# A607X.net
KiCad netlist of a schematic drawn in EAGLE
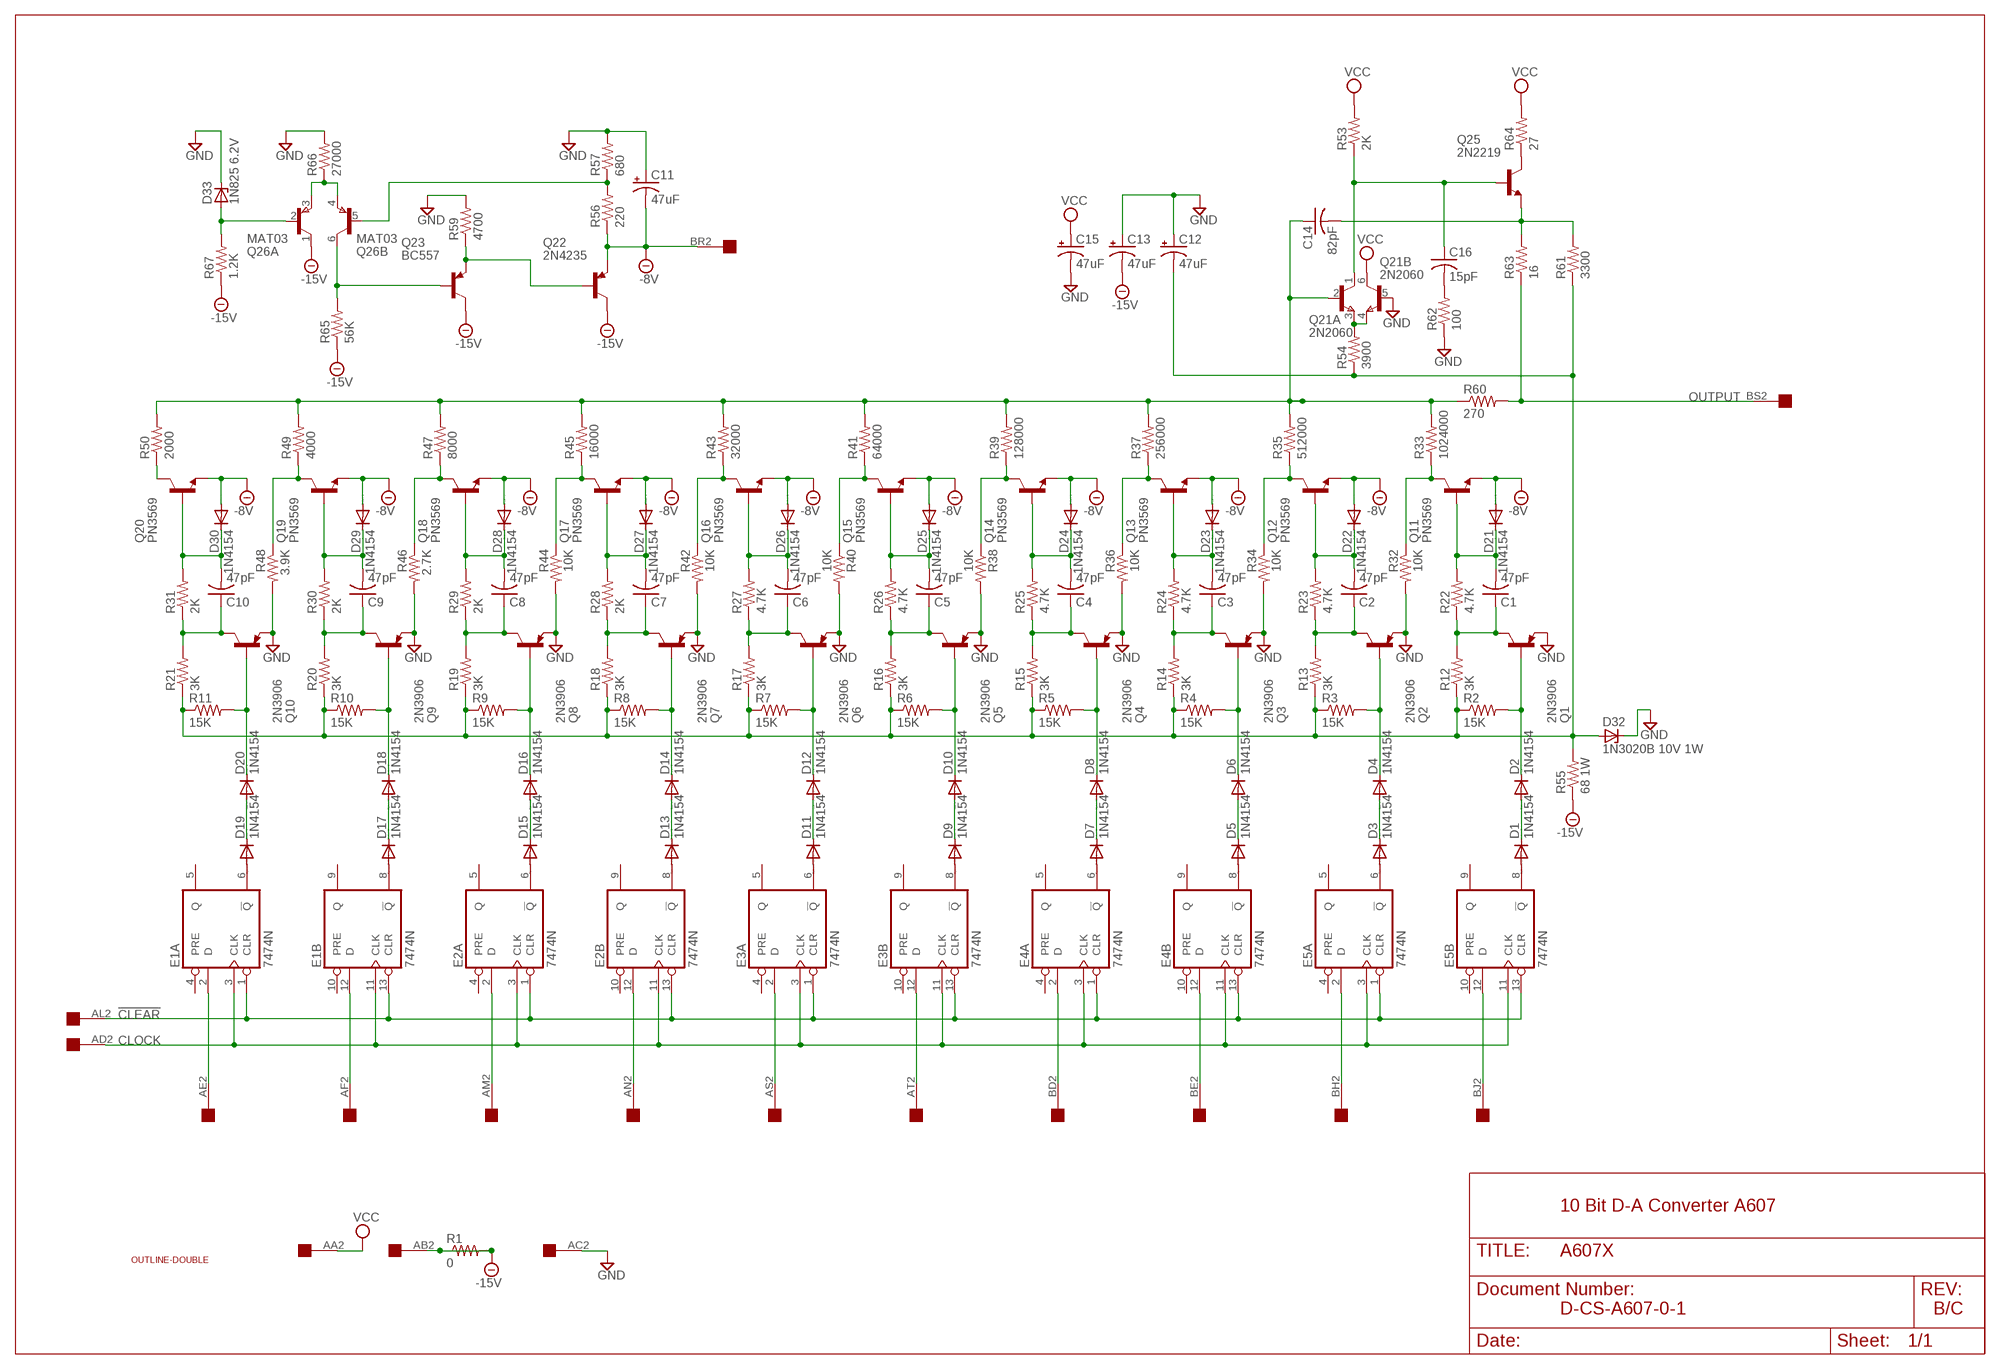
[diagram p0: schematic, sheet 1]

(export (version "E")
  (design (tool "Eeschema 10.0.6"))
  (components
    (comp (ref "C1")
      (value "47pF")
      (footprint "eagle-import:C075-032X103")
      (libsource (lib "eagle-import") (part "C-US075-032X103"))
    )
    (comp (ref "C2")
      (value "47pF")
      (footprint "eagle-import:C075-032X103")
      (libsource (lib "eagle-import") (part "C-US075-032X103"))
    )
    (comp (ref "C3")
      (value "47pF")
      (footprint "eagle-import:C075-032X103")
      (libsource (lib "eagle-import") (part "C-US075-032X103"))
    )
    (comp (ref "C4")
      (value "47pF")
      (footprint "eagle-import:C075-032X103")
      (libsource (lib "eagle-import") (part "C-US075-032X103"))
    )
    (comp (ref "C5")
      (value "47pF")
      (footprint "eagle-import:C075-032X103")
      (libsource (lib "eagle-import") (part "C-US075-032X103"))
    )
    (comp (ref "C6")
      (value "47pF")
      (footprint "eagle-import:C075-032X103")
      (libsource (lib "eagle-import") (part "C-US075-032X103"))
    )
    (comp (ref "C7")
      (value "47pF")
      (footprint "eagle-import:C075-032X103")
      (libsource (lib "eagle-import") (part "C-US075-032X103"))
    )
    (comp (ref "C8")
      (value "47pF")
      (footprint "eagle-import:C075-032X103")
      (libsource (lib "eagle-import") (part "C-US075-032X103"))
    )
    (comp (ref "C9")
      (value "47pF")
      (footprint "eagle-import:C075-032X103")
      (libsource (lib "eagle-import") (part "C-US075-032X103"))
    )
    (comp (ref "C10")
      (value "47pF")
      (footprint "eagle-import:C075-032X103")
      (libsource (lib "eagle-import") (part "C-US075-032X103"))
    )
    (comp (ref "C11")
      (value "47uF")
      (footprint "eagle-import:E25-9")
      (libsource (lib "eagle-import") (part "CPOL-USE25-9AXIAL"))
    )
    (comp (ref "C12")
      (value "47uF")
      (footprint "eagle-import:E25-9")
      (libsource (lib "eagle-import") (part "CPOL-USE25-9AXIAL"))
    )
    (comp (ref "C13")
      (value "47uF")
      (footprint "eagle-import:E25-9")
      (libsource (lib "eagle-import") (part "CPOL-USE25-9AXIAL"))
    )
    (comp (ref "C14")
      (value "82pF")
      (footprint "eagle-import:C050-025X075")
      (libsource (lib "eagle-import") (part "C-US050-025X075"))
    )
    (comp (ref "C15")
      (value "47uF")
      (footprint "eagle-import:E25-9")
      (libsource (lib "eagle-import") (part "CPOL-USE25-9AXIAL"))
    )
    (comp (ref "C16")
      (value "15pF")
      (footprint "eagle-import:C050-025X075")
      (libsource (lib "eagle-import") (part "C-US050-025X075"))
    )
    (comp (ref "D1")
      (value "1N4154")
      (footprint "eagle-import:DO35-10")
      (libsource (lib "eagle-import") (part "DIODE-DO35-10"))
    )
    (comp (ref "D2")
      (value "1N4154")
      (footprint "eagle-import:DO35-10")
      (libsource (lib "eagle-import") (part "DIODE-DO35-10"))
    )
    (comp (ref "D3")
      (value "1N4154")
      (footprint "eagle-import:DO35-10")
      (libsource (lib "eagle-import") (part "DIODE-DO35-10"))
    )
    (comp (ref "D4")
      (value "1N4154")
      (footprint "eagle-import:DO35-10")
      (libsource (lib "eagle-import") (part "DIODE-DO35-10"))
    )
    (comp (ref "D5")
      (value "1N4154")
      (footprint "eagle-import:DO35-10")
      (libsource (lib "eagle-import") (part "DIODE-DO35-10"))
    )
    (comp (ref "D6")
      (value "1N4154")
      (footprint "eagle-import:DO35-10")
      (libsource (lib "eagle-import") (part "DIODE-DO35-10"))
    )
    (comp (ref "D7")
      (value "1N4154")
      (footprint "eagle-import:DO35-10")
      (libsource (lib "eagle-import") (part "DIODE-DO35-10"))
    )
    (comp (ref "D8")
      (value "1N4154")
      (footprint "eagle-import:DO35-10")
      (libsource (lib "eagle-import") (part "DIODE-DO35-10"))
    )
    (comp (ref "D9")
      (value "1N4154")
      (footprint "eagle-import:DO35-10")
      (libsource (lib "eagle-import") (part "DIODE-DO35-10"))
    )
    (comp (ref "D10")
      (value "1N4154")
      (footprint "eagle-import:DO35-10")
      (libsource (lib "eagle-import") (part "DIODE-DO35-10"))
    )
    (comp (ref "D11")
      (value "1N4154")
      (footprint "eagle-import:DO35-10")
      (libsource (lib "eagle-import") (part "DIODE-DO35-10"))
    )
    (comp (ref "D12")
      (value "1N4154")
      (footprint "eagle-import:DO35-10")
      (libsource (lib "eagle-import") (part "DIODE-DO35-10"))
    )
    (comp (ref "D13")
      (value "1N4154")
      (footprint "eagle-import:DO35-10")
      (libsource (lib "eagle-import") (part "DIODE-DO35-10"))
    )
    (comp (ref "D14")
      (value "1N4154")
      (footprint "eagle-import:DO35-10")
      (libsource (lib "eagle-import") (part "DIODE-DO35-10"))
    )
    (comp (ref "D15")
      (value "1N4154")
      (footprint "eagle-import:DO35-10")
      (libsource (lib "eagle-import") (part "DIODE-DO35-10"))
    )
    (comp (ref "D16")
      (value "1N4154")
      (footprint "eagle-import:DO35-10")
      (libsource (lib "eagle-import") (part "DIODE-DO35-10"))
    )
    (comp (ref "D17")
      (value "1N4154")
      (footprint "eagle-import:DO35-10")
      (libsource (lib "eagle-import") (part "DIODE-DO35-10"))
    )
    (comp (ref "D18")
      (value "1N4154")
      (footprint "eagle-import:DO35-10")
      (libsource (lib "eagle-import") (part "DIODE-DO35-10"))
    )
    (comp (ref "D19")
      (value "1N4154")
      (footprint "eagle-import:DO35-10")
      (libsource (lib "eagle-import") (part "DIODE-DO35-10"))
    )
    (comp (ref "D20")
      (value "1N4154")
      (footprint "eagle-import:DO35-10")
      (libsource (lib "eagle-import") (part "DIODE-DO35-10"))
    )
    (comp (ref "D21")
      (value "1N4154")
      (footprint "eagle-import:DO35-10")
      (libsource (lib "eagle-import") (part "DIODE-DO35-10"))
    )
    (comp (ref "D22")
      (value "1N4154")
      (footprint "eagle-import:DO35-10")
      (libsource (lib "eagle-import") (part "DIODE-DO35-10"))
    )
    (comp (ref "D23")
      (value "1N4154")
      (footprint "eagle-import:DO35-10")
      (libsource (lib "eagle-import") (part "DIODE-DO35-10"))
    )
    (comp (ref "D24")
      (value "1N4154")
      (footprint "eagle-import:DO35-10")
      (libsource (lib "eagle-import") (part "DIODE-DO35-10"))
    )
    (comp (ref "D25")
      (value "1N4154")
      (footprint "eagle-import:DO35-10")
      (libsource (lib "eagle-import") (part "DIODE-DO35-10"))
    )
    (comp (ref "D26")
      (value "1N4154")
      (footprint "eagle-import:DO35-10")
      (libsource (lib "eagle-import") (part "DIODE-DO35-10"))
    )
    (comp (ref "D27")
      (value "1N4154")
      (footprint "eagle-import:DO35-10")
      (libsource (lib "eagle-import") (part "DIODE-DO35-10"))
    )
    (comp (ref "D28")
      (value "1N4154")
      (footprint "eagle-import:DO35-10")
      (libsource (lib "eagle-import") (part "DIODE-DO35-10"))
    )
    (comp (ref "D29")
      (value "1N4154")
      (footprint "eagle-import:DO35-10")
      (libsource (lib "eagle-import") (part "DIODE-DO35-10"))
    )
    (comp (ref "D30")
      (value "1N4154")
      (footprint "eagle-import:DO35-10")
      (libsource (lib "eagle-import") (part "DIODE-DO35-10"))
    )
    (comp (ref "D32")
      (value "1N3020B 10V 1W")
      (footprint "eagle-import:DO13M")
      (libsource (lib "eagle-import") (part "ZENER-DIODEDO13M"))
    )
    (comp (ref "D33")
      (value "1N825 6.2V")
      (footprint "eagle-import:DO35Z10")
      (libsource (lib "eagle-import") (part "ZENER-DIODEDO35Z10"))
    )
    (comp (ref "E1")
      (value "7474N")
      (footprint "eagle-import:DIL14")
      (libsource (lib "eagle-import") (part "7474NS"))
    )
    (comp (ref "E2")
      (value "7474N")
      (footprint "eagle-import:DIL14")
      (libsource (lib "eagle-import") (part "7474NS"))
    )
    (comp (ref "E3")
      (value "7474N")
      (footprint "eagle-import:DIL14")
      (libsource (lib "eagle-import") (part "7474NS"))
    )
    (comp (ref "E4")
      (value "7474N")
      (footprint "eagle-import:DIL14")
      (libsource (lib "eagle-import") (part "7474NS"))
    )
    (comp (ref "E5")
      (value "7474N")
      (footprint "eagle-import:DIL14")
      (libsource (lib "eagle-import") (part "7474NS"))
    )
    (comp (ref "Q1")
      (value "2N3906")
      (footprint "eagle-import:TO5")
      (libsource (lib "eagle-import") (part "-PNP-TO5"))
    )
    (comp (ref "Q2")
      (value "2N3906")
      (footprint "eagle-import:TO5")
      (libsource (lib "eagle-import") (part "-PNP-TO5"))
    )
    (comp (ref "Q3")
      (value "2N3906")
      (footprint "eagle-import:TO5")
      (libsource (lib "eagle-import") (part "-PNP-TO5"))
    )
    (comp (ref "Q4")
      (value "2N3906")
      (footprint "eagle-import:TO5")
      (libsource (lib "eagle-import") (part "-PNP-TO5"))
    )
    (comp (ref "Q5")
      (value "2N3906")
      (footprint "eagle-import:TO5")
      (libsource (lib "eagle-import") (part "-PNP-TO5"))
    )
    (comp (ref "Q6")
      (value "2N3906")
      (footprint "eagle-import:TO5")
      (libsource (lib "eagle-import") (part "-PNP-TO5"))
    )
    (comp (ref "Q7")
      (value "2N3906")
      (footprint "eagle-import:TO5")
      (libsource (lib "eagle-import") (part "-PNP-TO5"))
    )
    (comp (ref "Q8")
      (value "2N3906")
      (footprint "eagle-import:TO5")
      (libsource (lib "eagle-import") (part "-PNP-TO5"))
    )
    (comp (ref "Q9")
      (value "2N3906")
      (footprint "eagle-import:TO5")
      (libsource (lib "eagle-import") (part "-PNP-TO5"))
    )
    (comp (ref "Q10")
      (value "2N3906")
      (footprint "eagle-import:TO5")
      (libsource (lib "eagle-import") (part "-PNP-TO5"))
    )
    (comp (ref "Q11")
      (value "PN3569")
      (footprint "eagle-import:TO5")
      (libsource (lib "eagle-import") (part "-NPN-TO5"))
    )
    (comp (ref "Q12")
      (value "PN3569")
      (footprint "eagle-import:TO5")
      (libsource (lib "eagle-import") (part "-NPN-TO5"))
    )
    (comp (ref "Q13")
      (value "PN3569")
      (footprint "eagle-import:TO5")
      (libsource (lib "eagle-import") (part "-NPN-TO5"))
    )
    (comp (ref "Q14")
      (value "PN3569")
      (footprint "eagle-import:TO5")
      (libsource (lib "eagle-import") (part "-NPN-TO5"))
    )
    (comp (ref "Q15")
      (value "PN3569")
      (footprint "eagle-import:TO5")
      (libsource (lib "eagle-import") (part "-NPN-TO5"))
    )
    (comp (ref "Q16")
      (value "PN3569")
      (footprint "eagle-import:TO5")
      (libsource (lib "eagle-import") (part "-NPN-TO5"))
    )
    (comp (ref "Q17")
      (value "PN3569")
      (footprint "eagle-import:TO5")
      (libsource (lib "eagle-import") (part "-NPN-TO5"))
    )
    (comp (ref "Q18")
      (value "PN3569")
      (footprint "eagle-import:TO5")
      (libsource (lib "eagle-import") (part "-NPN-TO5"))
    )
    (comp (ref "Q19")
      (value "PN3569")
      (footprint "eagle-import:TO5")
      (libsource (lib "eagle-import") (part "-NPN-TO5"))
    )
    (comp (ref "Q20")
      (value "PN3569")
      (footprint "eagle-import:TO5")
      (libsource (lib "eagle-import") (part "-NPN-TO5"))
    )
    (comp (ref "Q21")
      (value "2N2060")
      (footprint "eagle-import:TO78")
      (libsource (lib "eagle-import") (part "MAT-02H"))
    )
    (comp (ref "Q22")
      (value "2N4235")
      (footprint "eagle-import:TO5")
      (libsource (lib "eagle-import") (part "-PNP-TO5"))
    )
    (comp (ref "Q23")
      (value "BC557")
      (footprint "eagle-import:TO5")
      (libsource (lib "eagle-import") (part "-PNP-TO5"))
    )
    (comp (ref "Q25")
      (value "2N2219")
      (footprint "eagle-import:TO5")
      (libsource (lib "eagle-import") (part "-NPN-TO5"))
    )
    (comp (ref "Q26")
      (value "MAT03")
      (footprint "eagle-import:TO78")
      (libsource (lib "eagle-import") (part "MAT-03H"))
    )
    (comp (ref "R1")
      (value "0")
      (footprint "eagle-import:0818_25")
      (libsource (lib "eagle-import") (part "R-US_0818/25"))
    )
    (comp (ref "R2")
      (value "15K")
      (footprint "eagle-import:0207_10")
      (libsource (lib "eagle-import") (part "R-US_0207/10"))
    )
    (comp (ref "R3")
      (value "15K")
      (footprint "eagle-import:0207_10")
      (libsource (lib "eagle-import") (part "R-US_0207/10"))
    )
    (comp (ref "R4")
      (value "15K")
      (footprint "eagle-import:0207_10")
      (libsource (lib "eagle-import") (part "R-US_0207/10"))
    )
    (comp (ref "R5")
      (value "15K")
      (footprint "eagle-import:0207_10")
      (libsource (lib "eagle-import") (part "R-US_0207/10"))
    )
    (comp (ref "R6")
      (value "15K")
      (footprint "eagle-import:0207_10")
      (libsource (lib "eagle-import") (part "R-US_0207/10"))
    )
    (comp (ref "R7")
      (value "15K")
      (footprint "eagle-import:0207_10")
      (libsource (lib "eagle-import") (part "R-US_0207/10"))
    )
    (comp (ref "R8")
      (value "15K")
      (footprint "eagle-import:0207_10")
      (libsource (lib "eagle-import") (part "R-US_0207/10"))
    )
    (comp (ref "R9")
      (value "15K")
      (footprint "eagle-import:0207_10")
      (libsource (lib "eagle-import") (part "R-US_0207/10"))
    )
    (comp (ref "R10")
      (value "15K")
      (footprint "eagle-import:0207_10")
      (libsource (lib "eagle-import") (part "R-US_0207/10"))
    )
    (comp (ref "R11")
      (value "15K")
      (footprint "eagle-import:0207_10")
      (libsource (lib "eagle-import") (part "R-US_0207/10"))
    )
    (comp (ref "R12")
      (value "3K")
      (footprint "eagle-import:0207_10")
      (libsource (lib "eagle-import") (part "R-US_0207/10"))
    )
    (comp (ref "R13")
      (value "3K")
      (footprint "eagle-import:0207_10")
      (libsource (lib "eagle-import") (part "R-US_0207/10"))
    )
    (comp (ref "R14")
      (value "3K")
      (footprint "eagle-import:0207_10")
      (libsource (lib "eagle-import") (part "R-US_0207/10"))
    )
    (comp (ref "R15")
      (value "3K")
      (footprint "eagle-import:0207_10")
      (libsource (lib "eagle-import") (part "R-US_0207/10"))
    )
    (comp (ref "R16")
      (value "3K")
      (footprint "eagle-import:0207_10")
      (libsource (lib "eagle-import") (part "R-US_0207/10"))
    )
    (comp (ref "R17")
      (value "3K")
      (footprint "eagle-import:0207_10")
      (libsource (lib "eagle-import") (part "R-US_0207/10"))
    )
    (comp (ref "R18")
      (value "3K")
      (footprint "eagle-import:0207_10")
      (libsource (lib "eagle-import") (part "R-US_0207/10"))
    )
    (comp (ref "R19")
      (value "3K")
      (footprint "eagle-import:0207_10")
      (libsource (lib "eagle-import") (part "R-US_0207/10"))
    )
    (comp (ref "R20")
      (value "3K")
      (footprint "eagle-import:0207_10")
      (libsource (lib "eagle-import") (part "R-US_0207/10"))
    )
    (comp (ref "R21")
      (value "3K")
      (footprint "eagle-import:0207_10")
      (libsource (lib "eagle-import") (part "R-US_0207/10"))
    )
    (comp (ref "R22")
      (value "4.7K")
      (footprint "eagle-import:0207_10")
      (libsource (lib "eagle-import") (part "R-US_0207/10"))
    )
    (comp (ref "R23")
      (value "4.7K")
      (footprint "eagle-import:0207_10")
      (libsource (lib "eagle-import") (part "R-US_0207/10"))
    )
    (comp (ref "R24")
      (value "4.7K")
      (footprint "eagle-import:0207_10")
      (libsource (lib "eagle-import") (part "R-US_0207/10"))
    )
    (comp (ref "R25")
      (value "4.7K")
      (footprint "eagle-import:0207_10")
      (libsource (lib "eagle-import") (part "R-US_0207/10"))
    )
    (comp (ref "R26")
      (value "4.7K")
      (footprint "eagle-import:0207_10")
      (libsource (lib "eagle-import") (part "R-US_0207/10"))
    )
    (comp (ref "R27")
      (value "4.7K")
      (footprint "eagle-import:0207_10")
      (libsource (lib "eagle-import") (part "R-US_0207/10"))
    )
    (comp (ref "R28")
      (value "2K")
      (footprint "eagle-import:0207_10")
      (libsource (lib "eagle-import") (part "R-US_0207/10"))
    )
    (comp (ref "R29")
      (value "2K")
      (footprint "eagle-import:0207_10")
      (libsource (lib "eagle-import") (part "R-US_0207/10"))
    )
    (comp (ref "R30")
      (value "2K")
      (footprint "eagle-import:0207_10")
      (libsource (lib "eagle-import") (part "R-US_0207/10"))
    )
    (comp (ref "R31")
      (value "2K")
      (footprint "eagle-import:0207_10")
      (libsource (lib "eagle-import") (part "R-US_0207/10"))
    )
    (comp (ref "R32")
      (value "10K")
      (footprint "eagle-import:0207_10")
      (libsource (lib "eagle-import") (part "R-US_0207/10"))
    )
    (comp (ref "R33")
      (value "1024000")
      (footprint "eagle-import:0414_20")
      (libsource (lib "eagle-import") (part "R-US_0414/20"))
    )
    (comp (ref "R34")
      (value "10K")
      (footprint "eagle-import:0207_10")
      (libsource (lib "eagle-import") (part "R-US_0207/10"))
    )
    (comp (ref "R35")
      (value "512000")
      (footprint "eagle-import:0414_20")
      (libsource (lib "eagle-import") (part "R-US_0414/20"))
    )
    (comp (ref "R36")
      (value "10K")
      (footprint "eagle-import:0207_10")
      (libsource (lib "eagle-import") (part "R-US_0207/10"))
    )
    (comp (ref "R37")
      (value "256000")
      (footprint "eagle-import:0207_15")
      (libsource (lib "eagle-import") (part "R-US_0207/15"))
    )
    (comp (ref "R38")
      (value "10K")
      (footprint "eagle-import:0207_10")
      (libsource (lib "eagle-import") (part "R-US_0207/10"))
    )
    (comp (ref "R39")
      (value "128000")
      (footprint "eagle-import:0207_15")
      (libsource (lib "eagle-import") (part "R-US_0207/15"))
    )
    (comp (ref "R40")
      (value "10K")
      (footprint "eagle-import:0207_10")
      (libsource (lib "eagle-import") (part "R-US_0207/10"))
    )
    (comp (ref "R41")
      (value "64000")
      (footprint "eagle-import:0207_15")
      (libsource (lib "eagle-import") (part "R-US_0207/15"))
    )
    (comp (ref "R42")
      (value "10K")
      (footprint "eagle-import:0207_10")
      (libsource (lib "eagle-import") (part "R-US_0207/10"))
    )
    (comp (ref "R43")
      (value "32000")
      (footprint "eagle-import:0207_15")
      (libsource (lib "eagle-import") (part "R-US_0207/15"))
    )
    (comp (ref "R44")
      (value "10K")
      (footprint "eagle-import:0207_10")
      (libsource (lib "eagle-import") (part "R-US_0207/10"))
    )
    (comp (ref "R45")
      (value "16000")
      (footprint "eagle-import:0207_15")
      (libsource (lib "eagle-import") (part "R-US_0207/15"))
    )
    (comp (ref "R46")
      (value "2.7K")
      (footprint "eagle-import:0207_10")
      (libsource (lib "eagle-import") (part "R-US_0207/10"))
    )
    (comp (ref "R47")
      (value "8000")
      (footprint "eagle-import:0207_15")
      (libsource (lib "eagle-import") (part "R-US_0207/15"))
    )
    (comp (ref "R48")
      (value "3.9K")
      (footprint "eagle-import:0207_10")
      (libsource (lib "eagle-import") (part "R-US_0207/10"))
    )
    (comp (ref "R49")
      (value "4000")
      (footprint "eagle-import:0207_15")
      (libsource (lib "eagle-import") (part "R-US_0207/15"))
    )
    (comp (ref "R50")
      (value "2000")
      (footprint "eagle-import:0207_15")
      (libsource (lib "eagle-import") (part "R-US_0207/15"))
    )
    (comp (ref "R53")
      (value "2K")
      (footprint "eagle-import:0207_10")
      (libsource (lib "eagle-import") (part "R-US_0207/10"))
    )
    (comp (ref "R54")
      (value "3900")
      (footprint "eagle-import:0207_10")
      (libsource (lib "eagle-import") (part "R-US_0207/10"))
    )
    (comp (ref "R55")
      (value "68 1W")
      (footprint "eagle-import:0818_25")
      (libsource (lib "eagle-import") (part "R-US_0818/25"))
    )
    (comp (ref "R56")
      (value "220")
      (footprint "eagle-import:0207_10")
      (libsource (lib "eagle-import") (part "R-US_0207/10"))
    )
    (comp (ref "R57")
      (value "680")
      (footprint "eagle-import:0207_10")
      (libsource (lib "eagle-import") (part "R-US_0207/10"))
    )
    (comp (ref "R59")
      (value "4700")
      (footprint "eagle-import:0207_10")
      (libsource (lib "eagle-import") (part "R-US_0207/10"))
    )
    (comp (ref "R60")
      (value "270")
      (footprint "eagle-import:0207_10")
      (libsource (lib "eagle-import") (part "R-US_0207/10"))
    )
    (comp (ref "R61")
      (value "3300")
      (footprint "eagle-import:0207_10")
      (libsource (lib "eagle-import") (part "R-US_0207/10"))
    )
    (comp (ref "R62")
      (value "100")
      (footprint "eagle-import:0207_10")
      (libsource (lib "eagle-import") (part "R-US_0207/10"))
    )
    (comp (ref "R63")
      (value "16")
      (footprint "eagle-import:0207_10")
      (libsource (lib "eagle-import") (part "R-US_0207/10"))
    )
    (comp (ref "R64")
      (value "27")
      (footprint "eagle-import:0207_10")
      (libsource (lib "eagle-import") (part "R-US_0207/10"))
    )
    (comp (ref "R65")
      (value "56K")
      (footprint "eagle-import:0207_10")
      (libsource (lib "eagle-import") (part "R-US_0207/10"))
    )
    (comp (ref "R66")
      (value "27000")
      (footprint "eagle-import:0207_10")
      (libsource (lib "eagle-import") (part "R-US_0207/10"))
    )
    (comp (ref "R67")
      (value "1.2K")
      (footprint "eagle-import:0207_10")
      (libsource (lib "eagle-import") (part "R-US_0207/10"))
    )
    (comp (ref "U$1")
      (value "OUTLINE-DOUBLE")
      (footprint "eagle-import:DOUBLE")
      (libsource (lib "eagle-import") (part "OUTLINE-DOUBLE"))
    )
    (comp (ref "U$2")
      (value "DOUBLE")
      (footprint "eagle-import:EDGE-CON4")
      (libsource (lib "eagle-import") (part "DOUBLE"))
    )
  )
  (nets
    (net (code "1") (name "-8V") (class "Default")
      (node (ref "C11") (pin "-") (pinfunction "-_-") (pintype "passive"))
      (node (ref "D21") (pin "A") (pinfunction "A_A") (pintype "passive"))
      (node (ref "D22") (pin "A") (pinfunction "A_A") (pintype "passive"))
      (node (ref "D23") (pin "A") (pinfunction "A_A") (pintype "passive"))
      (node (ref "D24") (pin "A") (pinfunction "A_A") (pintype "passive"))
      (node (ref "D25") (pin "A") (pinfunction "A_A") (pintype "passive"))
      (node (ref "D26") (pin "A") (pinfunction "A_A") (pintype "passive"))
      (node (ref "D27") (pin "A") (pinfunction "A_A") (pintype "passive"))
      (node (ref "D28") (pin "A") (pinfunction "A_A") (pintype "passive"))
      (node (ref "D29") (pin "A") (pinfunction "A_A") (pintype "passive"))
      (node (ref "D30") (pin "A") (pinfunction "A_A") (pintype "passive"))
      (node (ref "Q11") (pin "1") (pinfunction "E_1") (pintype "passive"))
      (node (ref "Q12") (pin "1") (pinfunction "E_1") (pintype "passive"))
      (node (ref "Q13") (pin "1") (pinfunction "E_1") (pintype "passive"))
      (node (ref "Q14") (pin "1") (pinfunction "E_1") (pintype "passive"))
      (node (ref "Q15") (pin "1") (pinfunction "E_1") (pintype "passive"))
      (node (ref "Q16") (pin "1") (pinfunction "E_1") (pintype "passive"))
      (node (ref "Q17") (pin "1") (pinfunction "E_1") (pintype "passive"))
      (node (ref "Q18") (pin "1") (pinfunction "E_1") (pintype "passive"))
      (node (ref "Q19") (pin "1") (pinfunction "E_1") (pintype "passive"))
      (node (ref "Q20") (pin "1") (pinfunction "E_1") (pintype "passive"))
      (node (ref "Q22") (pin "1") (pinfunction "E_1") (pintype "passive"))
      (node (ref "R56") (pin "1") (pinfunction "1_1") (pintype "passive"))
      (node (ref "U$2") (pin "BR2") (pinfunction "1_BR2") (pintype "bidirectional"))
    )
    (net (code "2") (name "-15V") (class "Default")
      (node (ref "C13") (pin "-") (pinfunction "-_-") (pintype "passive"))
      (node (ref "Q22") (pin "3") (pinfunction "C_3") (pintype "passive"))
      (node (ref "Q23") (pin "3") (pinfunction "C_3") (pintype "passive"))
      (node (ref "Q26") (pin "1") (pinfunction "C_1") (pintype "passive"))
      (node (ref "R1") (pin "1") (pinfunction "1_1") (pintype "passive"))
      (node (ref "R1") (pin "2") (pinfunction "2_2") (pintype "passive"))
      (node (ref "R55") (pin "1") (pinfunction "1_1") (pintype "passive"))
      (node (ref "R65") (pin "1") (pinfunction "1_1") (pintype "passive"))
      (node (ref "R67") (pin "1") (pinfunction "1_1") (pintype "passive"))
      (node (ref "U$2") (pin "AB2") (pinfunction "1_AB2") (pintype "bidirectional"))
    )
    (net (code "3") (name "/CLOCK") (class "Default")
      (node (ref "E1") (pin "11") (pinfunction "CLK_11") (pintype "input"))
      (node (ref "E1") (pin "3") (pinfunction "CLK_3") (pintype "input"))
      (node (ref "E2") (pin "11") (pinfunction "CLK_11") (pintype "input"))
      (node (ref "E2") (pin "3") (pinfunction "CLK_3") (pintype "input"))
      (node (ref "E3") (pin "11") (pinfunction "CLK_11") (pintype "input"))
      (node (ref "E3") (pin "3") (pinfunction "CLK_3") (pintype "input"))
      (node (ref "E4") (pin "11") (pinfunction "CLK_11") (pintype "input"))
      (node (ref "E4") (pin "3") (pinfunction "CLK_3") (pintype "input"))
      (node (ref "E5") (pin "11") (pinfunction "CLK_11") (pintype "input"))
      (node (ref "E5") (pin "3") (pinfunction "CLK_3") (pintype "input"))
      (node (ref "U$2") (pin "AD2") (pinfunction "1_AD2") (pintype "bidirectional"))
    )
    (net (code "4") (name "/OUTPUT") (class "Default")
      (node (ref "R60") (pin "2") (pinfunction "2_2") (pintype "passive"))
      (node (ref "R63") (pin "1") (pinfunction "1_1") (pintype "passive"))
      (node (ref "U$2") (pin "BS2") (pinfunction "1_BS2") (pintype "bidirectional"))
    )
    (net (code "5") (name "/~{CLEAR}") (class "Default")
      (node (ref "E1") (pin "1") (pinfunction "CLR_1") (pintype "input"))
      (node (ref "E1") (pin "13") (pinfunction "CLR_13") (pintype "input"))
      (node (ref "E2") (pin "1") (pinfunction "CLR_1") (pintype "input"))
      (node (ref "E2") (pin "13") (pinfunction "CLR_13") (pintype "input"))
      (node (ref "E3") (pin "1") (pinfunction "CLR_1") (pintype "input"))
      (node (ref "E3") (pin "13") (pinfunction "CLR_13") (pintype "input"))
      (node (ref "E4") (pin "1") (pinfunction "CLR_1") (pintype "input"))
      (node (ref "E4") (pin "13") (pinfunction "CLR_13") (pintype "input"))
      (node (ref "E5") (pin "1") (pinfunction "CLR_1") (pintype "input"))
      (node (ref "E5") (pin "13") (pinfunction "CLR_13") (pintype "input"))
      (node (ref "U$2") (pin "AL2") (pinfunction "1_AL2") (pintype "bidirectional"))
    )
    (net (code "6") (name "GND") (class "Default")
      (node (ref "C11") (pin "+") (pinfunction "+_+") (pintype "passive"))
      (node (ref "C12") (pin "+") (pinfunction "+_+") (pintype "passive"))
      (node (ref "C13") (pin "+") (pinfunction "+_+") (pintype "passive"))
      (node (ref "C15") (pin "-") (pinfunction "-_-") (pintype "passive"))
      (node (ref "D32") (pin "C") (pinfunction "C_C") (pintype "passive"))
      (node (ref "D33") (pin "C") (pinfunction "C_C") (pintype "passive"))
      (node (ref "Q1") (pin "1") (pinfunction "E_1") (pintype "passive"))
      (node (ref "Q10") (pin "1") (pinfunction "E_1") (pintype "passive"))
      (node (ref "Q2") (pin "1") (pinfunction "E_1") (pintype "passive"))
      (node (ref "Q21") (pin "5") (pinfunction "B_5") (pintype "passive"))
      (node (ref "Q3") (pin "1") (pinfunction "E_1") (pintype "passive"))
      (node (ref "Q4") (pin "1") (pinfunction "E_1") (pintype "passive"))
      (node (ref "Q5") (pin "1") (pinfunction "E_1") (pintype "passive"))
      (node (ref "Q6") (pin "1") (pinfunction "E_1") (pintype "passive"))
      (node (ref "Q7") (pin "1") (pinfunction "E_1") (pintype "passive"))
      (node (ref "Q8") (pin "1") (pinfunction "E_1") (pintype "passive"))
      (node (ref "Q9") (pin "1") (pinfunction "E_1") (pintype "passive"))
      (node (ref "R32") (pin "2") (pinfunction "2_2") (pintype "passive"))
      (node (ref "R34") (pin "2") (pinfunction "2_2") (pintype "passive"))
      (node (ref "R36") (pin "2") (pinfunction "2_2") (pintype "passive"))
      (node (ref "R38") (pin "2") (pinfunction "2_2") (pintype "passive"))
      (node (ref "R40") (pin "2") (pinfunction "2_2") (pintype "passive"))
      (node (ref "R42") (pin "2") (pinfunction "2_2") (pintype "passive"))
      (node (ref "R44") (pin "2") (pinfunction "2_2") (pintype "passive"))
      (node (ref "R46") (pin "2") (pinfunction "2_2") (pintype "passive"))
      (node (ref "R48") (pin "2") (pinfunction "2_2") (pintype "passive"))
      (node (ref "R57") (pin "2") (pinfunction "2_2") (pintype "passive"))
      (node (ref "R59") (pin "2") (pinfunction "2_2") (pintype "passive"))
      (node (ref "R62") (pin "1") (pinfunction "1_1") (pintype "passive"))
      (node (ref "R66") (pin "2") (pinfunction "2_2") (pintype "passive"))
      (node (ref "U$2") (pin "AC2") (pinfunction "1_AC2") (pintype "bidirectional"))
    )
    (net (code "7") (name "Net-(C12-Pad-)") (class "Default")
      (node (ref "C12") (pin "-") (pinfunction "-_-") (pintype "passive"))
      (node (ref "D32") (pin "A") (pinfunction "A_A") (pintype "passive"))
      (node (ref "R10") (pin "1") (pinfunction "1_1") (pintype "passive"))
      (node (ref "R11") (pin "1") (pinfunction "1_1") (pintype "passive"))
      (node (ref "R12") (pin "1") (pinfunction "1_1") (pintype "passive"))
      (node (ref "R13") (pin "1") (pinfunction "1_1") (pintype "passive"))
      (node (ref "R14") (pin "1") (pinfunction "1_1") (pintype "passive"))
      (node (ref "R15") (pin "1") (pinfunction "1_1") (pintype "passive"))
      (node (ref "R16") (pin "1") (pinfunction "1_1") (pintype "passive"))
      (node (ref "R17") (pin "1") (pinfunction "1_1") (pintype "passive"))
      (node (ref "R18") (pin "1") (pinfunction "1_1") (pintype "passive"))
      (node (ref "R19") (pin "1") (pinfunction "1_1") (pintype "passive"))
      (node (ref "R2") (pin "1") (pinfunction "1_1") (pintype "passive"))
      (node (ref "R20") (pin "1") (pinfunction "1_1") (pintype "passive"))
      (node (ref "R21") (pin "1") (pinfunction "1_1") (pintype "passive"))
      (node (ref "R3") (pin "1") (pinfunction "1_1") (pintype "passive"))
      (node (ref "R4") (pin "1") (pinfunction "1_1") (pintype "passive"))
      (node (ref "R5") (pin "1") (pinfunction "1_1") (pintype "passive"))
      (node (ref "R54") (pin "1") (pinfunction "1_1") (pintype "passive"))
      (node (ref "R55") (pin "2") (pinfunction "2_2") (pintype "passive"))
      (node (ref "R6") (pin "1") (pinfunction "1_1") (pintype "passive"))
      (node (ref "R61") (pin "1") (pinfunction "1_1") (pintype "passive"))
      (node (ref "R7") (pin "1") (pinfunction "1_1") (pintype "passive"))
      (node (ref "R8") (pin "1") (pinfunction "1_1") (pintype "passive"))
      (node (ref "R9") (pin "1") (pinfunction "1_1") (pintype "passive"))
    )
    (net (code "8") (name "Net-(C16-Pad2)") (class "Default")
      (node (ref "C16") (pin "2") (pinfunction "2_2") (pintype "passive"))
      (node (ref "R62") (pin "2") (pinfunction "2_2") (pintype "passive"))
    )
    (net (code "9") (name "Net-(D1-PadC)") (class "Default")
      (node (ref "D1") (pin "C") (pinfunction "C_C") (pintype "passive"))
      (node (ref "D2") (pin "A") (pinfunction "A_A") (pintype "passive"))
    )
    (net (code "10") (name "Net-(D3-PadC)") (class "Default")
      (node (ref "D3") (pin "C") (pinfunction "C_C") (pintype "passive"))
      (node (ref "D4") (pin "A") (pinfunction "A_A") (pintype "passive"))
    )
    (net (code "11") (name "Net-(D5-PadC)") (class "Default")
      (node (ref "D5") (pin "C") (pinfunction "C_C") (pintype "passive"))
      (node (ref "D6") (pin "A") (pinfunction "A_A") (pintype "passive"))
    )
    (net (code "12") (name "Net-(D7-PadC)") (class "Default")
      (node (ref "D7") (pin "C") (pinfunction "C_C") (pintype "passive"))
      (node (ref "D8") (pin "A") (pinfunction "A_A") (pintype "passive"))
    )
    (net (code "13") (name "Net-(D10-PadA)") (class "Default")
      (node (ref "D10") (pin "A") (pinfunction "A_A") (pintype "passive"))
      (node (ref "D9") (pin "C") (pinfunction "C_C") (pintype "passive"))
    )
    (net (code "14") (name "Net-(D11-PadC)") (class "Default")
      (node (ref "D11") (pin "C") (pinfunction "C_C") (pintype "passive"))
      (node (ref "D12") (pin "A") (pinfunction "A_A") (pintype "passive"))
    )
    (net (code "15") (name "Net-(D13-PadC)") (class "Default")
      (node (ref "D13") (pin "C") (pinfunction "C_C") (pintype "passive"))
      (node (ref "D14") (pin "A") (pinfunction "A_A") (pintype "passive"))
    )
    (net (code "16") (name "Net-(D15-PadC)") (class "Default")
      (node (ref "D15") (pin "C") (pinfunction "C_C") (pintype "passive"))
      (node (ref "D16") (pin "A") (pinfunction "A_A") (pintype "passive"))
    )
    (net (code "17") (name "Net-(D17-PadC)") (class "Default")
      (node (ref "D17") (pin "C") (pinfunction "C_C") (pintype "passive"))
      (node (ref "D18") (pin "A") (pinfunction "A_A") (pintype "passive"))
    )
    (net (code "18") (name "Net-(D19-PadC)") (class "Default")
      (node (ref "D19") (pin "C") (pinfunction "C_C") (pintype "passive"))
      (node (ref "D20") (pin "A") (pinfunction "A_A") (pintype "passive"))
    )
    (net (code "19") (name "Net-(E1A-D)") (class "Default")
      (node (ref "E1") (pin "2") (pinfunction "D_2") (pintype "input"))
      (node (ref "U$2") (pin "AE2") (pinfunction "1_AE2") (pintype "bidirectional"))
    )
    (net (code "20") (name "Net-(E1A-~{Q})") (class "Default")
      (node (ref "D19") (pin "A") (pinfunction "A_A") (pintype "passive"))
      (node (ref "E1") (pin "6") (pinfunction "~{Q}_6") (pintype "output"))
    )
    (net (code "21") (name "Net-(E1B-D)") (class "Default")
      (node (ref "E1") (pin "12") (pinfunction "D_12") (pintype "input"))
      (node (ref "U$2") (pin "AF2") (pinfunction "1_AF2") (pintype "bidirectional"))
    )
    (net (code "22") (name "Net-(E1B-~{Q})") (class "Default")
      (node (ref "D17") (pin "A") (pinfunction "A_A") (pintype "passive"))
      (node (ref "E1") (pin "8") (pinfunction "~{Q}_8") (pintype "output"))
    )
    (net (code "23") (name "Net-(E2A-D)") (class "Default")
      (node (ref "E2") (pin "2") (pinfunction "D_2") (pintype "input"))
      (node (ref "U$2") (pin "AM2") (pinfunction "1_AM2") (pintype "bidirectional"))
    )
    (net (code "24") (name "Net-(E2A-~{Q})") (class "Default")
      (node (ref "D15") (pin "A") (pinfunction "A_A") (pintype "passive"))
      (node (ref "E2") (pin "6") (pinfunction "~{Q}_6") (pintype "output"))
    )
    (net (code "25") (name "Net-(E2B-D)") (class "Default")
      (node (ref "E2") (pin "12") (pinfunction "D_12") (pintype "input"))
      (node (ref "U$2") (pin "AN2") (pinfunction "1_AN2") (pintype "bidirectional"))
    )
    (net (code "26") (name "Net-(E2B-~{Q})") (class "Default")
      (node (ref "D13") (pin "A") (pinfunction "A_A") (pintype "passive"))
      (node (ref "E2") (pin "8") (pinfunction "~{Q}_8") (pintype "output"))
    )
    (net (code "27") (name "Net-(E3A-D)") (class "Default")
      (node (ref "E3") (pin "2") (pinfunction "D_2") (pintype "input"))
      (node (ref "U$2") (pin "AS2") (pinfunction "1_AS2") (pintype "bidirectional"))
    )
    (net (code "28") (name "Net-(E3A-~{Q})") (class "Default")
      (node (ref "D11") (pin "A") (pinfunction "A_A") (pintype "passive"))
      (node (ref "E3") (pin "6") (pinfunction "~{Q}_6") (pintype "output"))
    )
    (net (code "29") (name "Net-(E3B-D)") (class "Default")
      (node (ref "E3") (pin "12") (pinfunction "D_12") (pintype "input"))
      (node (ref "U$2") (pin "AT2") (pinfunction "1_AT2") (pintype "bidirectional"))
    )
    (net (code "30") (name "Net-(E3B-~{Q})") (class "Default")
      (node (ref "D9") (pin "A") (pinfunction "A_A") (pintype "passive"))
      (node (ref "E3") (pin "8") (pinfunction "~{Q}_8") (pintype "output"))
    )
    (net (code "31") (name "Net-(E4A-D)") (class "Default")
      (node (ref "E4") (pin "2") (pinfunction "D_2") (pintype "input"))
      (node (ref "U$2") (pin "BD2") (pinfunction "1_BD2") (pintype "bidirectional"))
    )
    (net (code "32") (name "Net-(E4A-~{Q})") (class "Default")
      (node (ref "D7") (pin "A") (pinfunction "A_A") (pintype "passive"))
      (node (ref "E4") (pin "6") (pinfunction "~{Q}_6") (pintype "output"))
    )
    (net (code "33") (name "Net-(E4B-D)") (class "Default")
      (node (ref "E4") (pin "12") (pinfunction "D_12") (pintype "input"))
      (node (ref "U$2") (pin "BE2") (pinfunction "1_BE2") (pintype "bidirectional"))
    )
    (net (code "34") (name "Net-(E4B-~{Q})") (class "Default")
      (node (ref "D5") (pin "A") (pinfunction "A_A") (pintype "passive"))
      (node (ref "E4") (pin "8") (pinfunction "~{Q}_8") (pintype "output"))
    )
    (net (code "35") (name "Net-(E5A-D)") (class "Default")
      (node (ref "E5") (pin "2") (pinfunction "D_2") (pintype "input"))
      (node (ref "U$2") (pin "BH2") (pinfunction "1_BH2") (pintype "bidirectional"))
    )
    (net (code "36") (name "Net-(E5A-~{Q})") (class "Default")
      (node (ref "D3") (pin "A") (pinfunction "A_A") (pintype "passive"))
      (node (ref "E5") (pin "6") (pinfunction "~{Q}_6") (pintype "output"))
    )
    (net (code "37") (name "Net-(E5B-D)") (class "Default")
      (node (ref "E5") (pin "12") (pinfunction "D_12") (pintype "input"))
      (node (ref "U$2") (pin "BJ2") (pinfunction "1_BJ2") (pintype "bidirectional"))
    )
    (net (code "38") (name "Net-(E5B-~{Q})") (class "Default")
      (node (ref "D1") (pin "A") (pinfunction "A_A") (pintype "passive"))
      (node (ref "E5") (pin "8") (pinfunction "~{Q}_8") (pintype "output"))
    )
    (net (code "39") (name "Net-(Q1-B)") (class "Default")
      (node (ref "D2") (pin "C") (pinfunction "C_C") (pintype "passive"))
      (node (ref "Q1") (pin "2") (pinfunction "B_2") (pintype "passive"))
      (node (ref "R2") (pin "2") (pinfunction "2_2") (pintype "passive"))
    )
    (net (code "40") (name "Net-(Q1-C)") (class "Default")
      (node (ref "C1") (pin "1") (pinfunction "1_1") (pintype "passive"))
      (node (ref "Q1") (pin "3") (pinfunction "C_3") (pintype "passive"))
      (node (ref "R12") (pin "2") (pinfunction "2_2") (pintype "passive"))
      (node (ref "R22") (pin "1") (pinfunction "1_1") (pintype "passive"))
    )
    (net (code "41") (name "Net-(Q2-B)") (class "Default")
      (node (ref "D4") (pin "C") (pinfunction "C_C") (pintype "passive"))
      (node (ref "Q2") (pin "2") (pinfunction "B_2") (pintype "passive"))
      (node (ref "R3") (pin "2") (pinfunction "2_2") (pintype "passive"))
    )
    (net (code "42") (name "Net-(Q2-C)") (class "Default")
      (node (ref "C2") (pin "1") (pinfunction "1_1") (pintype "passive"))
      (node (ref "Q2") (pin "3") (pinfunction "C_3") (pintype "passive"))
      (node (ref "R13") (pin "2") (pinfunction "2_2") (pintype "passive"))
      (node (ref "R23") (pin "1") (pinfunction "1_1") (pintype "passive"))
    )
    (net (code "43") (name "Net-(Q3-B)") (class "Default")
      (node (ref "D6") (pin "C") (pinfunction "C_C") (pintype "passive"))
      (node (ref "Q3") (pin "2") (pinfunction "B_2") (pintype "passive"))
      (node (ref "R4") (pin "2") (pinfunction "2_2") (pintype "passive"))
    )
    (net (code "44") (name "Net-(Q3-C)") (class "Default")
      (node (ref "C3") (pin "1") (pinfunction "1_1") (pintype "passive"))
      (node (ref "Q3") (pin "3") (pinfunction "C_3") (pintype "passive"))
      (node (ref "R14") (pin "2") (pinfunction "2_2") (pintype "passive"))
      (node (ref "R24") (pin "1") (pinfunction "1_1") (pintype "passive"))
    )
    (net (code "45") (name "Net-(Q4-B)") (class "Default")
      (node (ref "D8") (pin "C") (pinfunction "C_C") (pintype "passive"))
      (node (ref "Q4") (pin "2") (pinfunction "B_2") (pintype "passive"))
      (node (ref "R5") (pin "2") (pinfunction "2_2") (pintype "passive"))
    )
    (net (code "46") (name "Net-(Q4-C)") (class "Default")
      (node (ref "C4") (pin "1") (pinfunction "1_1") (pintype "passive"))
      (node (ref "Q4") (pin "3") (pinfunction "C_3") (pintype "passive"))
      (node (ref "R15") (pin "2") (pinfunction "2_2") (pintype "passive"))
      (node (ref "R25") (pin "1") (pinfunction "1_1") (pintype "passive"))
    )
    (net (code "47") (name "Net-(Q5-B)") (class "Default")
      (node (ref "D10") (pin "C") (pinfunction "C_C") (pintype "passive"))
      (node (ref "Q5") (pin "2") (pinfunction "B_2") (pintype "passive"))
      (node (ref "R6") (pin "2") (pinfunction "2_2") (pintype "passive"))
    )
    (net (code "48") (name "Net-(Q5-C)") (class "Default")
      (node (ref "C5") (pin "1") (pinfunction "1_1") (pintype "passive"))
      (node (ref "Q5") (pin "3") (pinfunction "C_3") (pintype "passive"))
      (node (ref "R16") (pin "2") (pinfunction "2_2") (pintype "passive"))
      (node (ref "R26") (pin "1") (pinfunction "1_1") (pintype "passive"))
    )
    (net (code "49") (name "Net-(Q6-B)") (class "Default")
      (node (ref "D12") (pin "C") (pinfunction "C_C") (pintype "passive"))
      (node (ref "Q6") (pin "2") (pinfunction "B_2") (pintype "passive"))
      (node (ref "R7") (pin "2") (pinfunction "2_2") (pintype "passive"))
    )
    (net (code "50") (name "Net-(Q6-C)") (class "Default")
      (node (ref "C6") (pin "1") (pinfunction "1_1") (pintype "passive"))
      (node (ref "Q6") (pin "3") (pinfunction "C_3") (pintype "passive"))
      (node (ref "R17") (pin "2") (pinfunction "2_2") (pintype "passive"))
      (node (ref "R27") (pin "1") (pinfunction "1_1") (pintype "passive"))
    )
    (net (code "51") (name "Net-(Q7-B)") (class "Default")
      (node (ref "D14") (pin "C") (pinfunction "C_C") (pintype "passive"))
      (node (ref "Q7") (pin "2") (pinfunction "B_2") (pintype "passive"))
      (node (ref "R8") (pin "2") (pinfunction "2_2") (pintype "passive"))
    )
    (net (code "52") (name "Net-(Q7-C)") (class "Default")
      (node (ref "C7") (pin "1") (pinfunction "1_1") (pintype "passive"))
      (node (ref "Q7") (pin "3") (pinfunction "C_3") (pintype "passive"))
      (node (ref "R18") (pin "2") (pinfunction "2_2") (pintype "passive"))
      (node (ref "R28") (pin "1") (pinfunction "1_1") (pintype "passive"))
    )
    (net (code "53") (name "Net-(Q8-B)") (class "Default")
      (node (ref "D16") (pin "C") (pinfunction "C_C") (pintype "passive"))
      (node (ref "Q8") (pin "2") (pinfunction "B_2") (pintype "passive"))
      (node (ref "R9") (pin "2") (pinfunction "2_2") (pintype "passive"))
    )
    (net (code "54") (name "Net-(Q8-C)") (class "Default")
      (node (ref "C8") (pin "1") (pinfunction "1_1") (pintype "passive"))
      (node (ref "Q8") (pin "3") (pinfunction "C_3") (pintype "passive"))
      (node (ref "R19") (pin "2") (pinfunction "2_2") (pintype "passive"))
      (node (ref "R29") (pin "1") (pinfunction "1_1") (pintype "passive"))
    )
    (net (code "55") (name "Net-(Q9-B)") (class "Default")
      (node (ref "D18") (pin "C") (pinfunction "C_C") (pintype "passive"))
      (node (ref "Q9") (pin "2") (pinfunction "B_2") (pintype "passive"))
      (node (ref "R10") (pin "2") (pinfunction "2_2") (pintype "passive"))
    )
    (net (code "56") (name "Net-(Q9-C)") (class "Default")
      (node (ref "C9") (pin "1") (pinfunction "1_1") (pintype "passive"))
      (node (ref "Q9") (pin "3") (pinfunction "C_3") (pintype "passive"))
      (node (ref "R20") (pin "2") (pinfunction "2_2") (pintype "passive"))
      (node (ref "R30") (pin "1") (pinfunction "1_1") (pintype "passive"))
    )
    (net (code "57") (name "Net-(Q10-B)") (class "Default")
      (node (ref "D20") (pin "C") (pinfunction "C_C") (pintype "passive"))
      (node (ref "Q10") (pin "2") (pinfunction "B_2") (pintype "passive"))
      (node (ref "R11") (pin "2") (pinfunction "2_2") (pintype "passive"))
    )
    (net (code "58") (name "Net-(Q10-C)") (class "Default")
      (node (ref "C10") (pin "1") (pinfunction "1_1") (pintype "passive"))
      (node (ref "Q10") (pin "3") (pinfunction "C_3") (pintype "passive"))
      (node (ref "R21") (pin "2") (pinfunction "2_2") (pintype "passive"))
      (node (ref "R31") (pin "1") (pinfunction "1_1") (pintype "passive"))
    )
    (net (code "59") (name "Net-(Q11-B)") (class "Default")
      (node (ref "C1") (pin "2") (pinfunction "2_2") (pintype "passive"))
      (node (ref "D21") (pin "C") (pinfunction "C_C") (pintype "passive"))
      (node (ref "Q11") (pin "2") (pinfunction "B_2") (pintype "passive"))
      (node (ref "R22") (pin "2") (pinfunction "2_2") (pintype "passive"))
    )
    (net (code "60") (name "Net-(Q11-C)") (class "Default")
      (node (ref "Q11") (pin "3") (pinfunction "C_3") (pintype "passive"))
      (node (ref "R32") (pin "1") (pinfunction "1_1") (pintype "passive"))
      (node (ref "R33") (pin "1") (pinfunction "1_1") (pintype "passive"))
    )
    (net (code "61") (name "Net-(Q12-B)") (class "Default")
      (node (ref "C2") (pin "2") (pinfunction "2_2") (pintype "passive"))
      (node (ref "D22") (pin "C") (pinfunction "C_C") (pintype "passive"))
      (node (ref "Q12") (pin "2") (pinfunction "B_2") (pintype "passive"))
      (node (ref "R23") (pin "2") (pinfunction "2_2") (pintype "passive"))
    )
    (net (code "62") (name "Net-(Q12-C)") (class "Default")
      (node (ref "Q12") (pin "3") (pinfunction "C_3") (pintype "passive"))
      (node (ref "R34") (pin "1") (pinfunction "1_1") (pintype "passive"))
      (node (ref "R35") (pin "1") (pinfunction "1_1") (pintype "passive"))
    )
    (net (code "63") (name "Net-(Q13-B)") (class "Default")
      (node (ref "C3") (pin "2") (pinfunction "2_2") (pintype "passive"))
      (node (ref "D23") (pin "C") (pinfunction "C_C") (pintype "passive"))
      (node (ref "Q13") (pin "2") (pinfunction "B_2") (pintype "passive"))
      (node (ref "R24") (pin "2") (pinfunction "2_2") (pintype "passive"))
    )
    (net (code "64") (name "Net-(Q13-C)") (class "Default")
      (node (ref "Q13") (pin "3") (pinfunction "C_3") (pintype "passive"))
      (node (ref "R36") (pin "1") (pinfunction "1_1") (pintype "passive"))
      (node (ref "R37") (pin "1") (pinfunction "1_1") (pintype "passive"))
    )
    (net (code "65") (name "Net-(Q14-B)") (class "Default")
      (node (ref "C4") (pin "2") (pinfunction "2_2") (pintype "passive"))
      (node (ref "D24") (pin "C") (pinfunction "C_C") (pintype "passive"))
      (node (ref "Q14") (pin "2") (pinfunction "B_2") (pintype "passive"))
      (node (ref "R25") (pin "2") (pinfunction "2_2") (pintype "passive"))
    )
    (net (code "66") (name "Net-(Q14-C)") (class "Default")
      (node (ref "Q14") (pin "3") (pinfunction "C_3") (pintype "passive"))
      (node (ref "R38") (pin "1") (pinfunction "1_1") (pintype "passive"))
      (node (ref "R39") (pin "1") (pinfunction "1_1") (pintype "passive"))
    )
    (net (code "67") (name "Net-(Q15-B)") (class "Default")
      (node (ref "C5") (pin "2") (pinfunction "2_2") (pintype "passive"))
      (node (ref "D25") (pin "C") (pinfunction "C_C") (pintype "passive"))
      (node (ref "Q15") (pin "2") (pinfunction "B_2") (pintype "passive"))
      (node (ref "R26") (pin "2") (pinfunction "2_2") (pintype "passive"))
    )
    (net (code "68") (name "Net-(Q15-C)") (class "Default")
      (node (ref "Q15") (pin "3") (pinfunction "C_3") (pintype "passive"))
      (node (ref "R40") (pin "1") (pinfunction "1_1") (pintype "passive"))
      (node (ref "R41") (pin "1") (pinfunction "1_1") (pintype "passive"))
    )
    (net (code "69") (name "Net-(Q16-B)") (class "Default")
      (node (ref "C6") (pin "2") (pinfunction "2_2") (pintype "passive"))
      (node (ref "D26") (pin "C") (pinfunction "C_C") (pintype "passive"))
      (node (ref "Q16") (pin "2") (pinfunction "B_2") (pintype "passive"))
      (node (ref "R27") (pin "2") (pinfunction "2_2") (pintype "passive"))
    )
    (net (code "70") (name "Net-(Q16-C)") (class "Default")
      (node (ref "Q16") (pin "3") (pinfunction "C_3") (pintype "passive"))
      (node (ref "R42") (pin "1") (pinfunction "1_1") (pintype "passive"))
      (node (ref "R43") (pin "1") (pinfunction "1_1") (pintype "passive"))
    )
    (net (code "71") (name "Net-(Q17-B)") (class "Default")
      (node (ref "C7") (pin "2") (pinfunction "2_2") (pintype "passive"))
      (node (ref "D27") (pin "C") (pinfunction "C_C") (pintype "passive"))
      (node (ref "Q17") (pin "2") (pinfunction "B_2") (pintype "passive"))
      (node (ref "R28") (pin "2") (pinfunction "2_2") (pintype "passive"))
    )
    (net (code "72") (name "Net-(Q17-C)") (class "Default")
      (node (ref "Q17") (pin "3") (pinfunction "C_3") (pintype "passive"))
      (node (ref "R44") (pin "1") (pinfunction "1_1") (pintype "passive"))
      (node (ref "R45") (pin "1") (pinfunction "1_1") (pintype "passive"))
    )
    (net (code "73") (name "Net-(Q18-B)") (class "Default")
      (node (ref "C8") (pin "2") (pinfunction "2_2") (pintype "passive"))
      (node (ref "D28") (pin "C") (pinfunction "C_C") (pintype "passive"))
      (node (ref "Q18") (pin "2") (pinfunction "B_2") (pintype "passive"))
      (node (ref "R29") (pin "2") (pinfunction "2_2") (pintype "passive"))
    )
    (net (code "74") (name "Net-(Q18-C)") (class "Default")
      (node (ref "Q18") (pin "3") (pinfunction "C_3") (pintype "passive"))
      (node (ref "R46") (pin "1") (pinfunction "1_1") (pintype "passive"))
      (node (ref "R47") (pin "1") (pinfunction "1_1") (pintype "passive"))
    )
    (net (code "75") (name "Net-(Q19-B)") (class "Default")
      (node (ref "C9") (pin "2") (pinfunction "2_2") (pintype "passive"))
      (node (ref "D29") (pin "C") (pinfunction "C_C") (pintype "passive"))
      (node (ref "Q19") (pin "2") (pinfunction "B_2") (pintype "passive"))
      (node (ref "R30") (pin "2") (pinfunction "2_2") (pintype "passive"))
    )
    (net (code "76") (name "Net-(Q19-C)") (class "Default")
      (node (ref "Q19") (pin "3") (pinfunction "C_3") (pintype "passive"))
      (node (ref "R48") (pin "1") (pinfunction "1_1") (pintype "passive"))
      (node (ref "R49") (pin "1") (pinfunction "1_1") (pintype "passive"))
    )
    (net (code "77") (name "Net-(Q20-B)") (class "Default")
      (node (ref "C10") (pin "2") (pinfunction "2_2") (pintype "passive"))
      (node (ref "D30") (pin "C") (pinfunction "C_C") (pintype "passive"))
      (node (ref "Q20") (pin "2") (pinfunction "B_2") (pintype "passive"))
      (node (ref "R31") (pin "2") (pinfunction "2_2") (pintype "passive"))
    )
    (net (code "78") (name "Net-(Q20-C)") (class "Default")
      (node (ref "Q20") (pin "3") (pinfunction "C_3") (pintype "passive"))
      (node (ref "R50") (pin "1") (pinfunction "1_1") (pintype "passive"))
    )
    (net (code "79") (name "Net-(Q21A-B)") (class "Default")
      (node (ref "C14") (pin "1") (pinfunction "1_1") (pintype "passive"))
      (node (ref "Q21") (pin "2") (pinfunction "B_2") (pintype "passive"))
      (node (ref "R33") (pin "2") (pinfunction "2_2") (pintype "passive"))
      (node (ref "R35") (pin "2") (pinfunction "2_2") (pintype "passive"))
      (node (ref "R37") (pin "2") (pinfunction "2_2") (pintype "passive"))
      (node (ref "R39") (pin "2") (pinfunction "2_2") (pintype "passive"))
      (node (ref "R41") (pin "2") (pinfunction "2_2") (pintype "passive"))
      (node (ref "R43") (pin "2") (pinfunction "2_2") (pintype "passive"))
      (node (ref "R45") (pin "2") (pinfunction "2_2") (pintype "passive"))
      (node (ref "R47") (pin "2") (pinfunction "2_2") (pintype "passive"))
      (node (ref "R49") (pin "2") (pinfunction "2_2") (pintype "passive"))
      (node (ref "R50") (pin "2") (pinfunction "2_2") (pintype "passive"))
      (node (ref "R60") (pin "1") (pinfunction "1_1") (pintype "passive"))
    )
    (net (code "80") (name "Net-(Q21A-C)") (class "Default")
      (node (ref "C16") (pin "1") (pinfunction "1_1") (pintype "passive"))
      (node (ref "Q21") (pin "1") (pinfunction "C_1") (pintype "passive"))
      (node (ref "Q25") (pin "2") (pinfunction "B_2") (pintype "passive"))
      (node (ref "R53") (pin "1") (pinfunction "1_1") (pintype "passive"))
    )
    (net (code "81") (name "Net-(Q21A-E)") (class "Default")
      (node (ref "Q21") (pin "3") (pinfunction "E_3") (pintype "passive"))
      (node (ref "Q21") (pin "4") (pinfunction "E_4") (pintype "passive"))
      (node (ref "R54") (pin "2") (pinfunction "2_2") (pintype "passive"))
    )
    (net (code "82") (name "Net-(Q22-B)") (class "Default")
      (node (ref "Q22") (pin "2") (pinfunction "B_2") (pintype "passive"))
      (node (ref "Q23") (pin "1") (pinfunction "E_1") (pintype "passive"))
      (node (ref "R59") (pin "1") (pinfunction "1_1") (pintype "passive"))
    )
    (net (code "83") (name "Net-(Q23-B)") (class "Default")
      (node (ref "Q23") (pin "2") (pinfunction "B_2") (pintype "passive"))
      (node (ref "Q26") (pin "6") (pinfunction "C_6") (pintype "passive"))
      (node (ref "R65") (pin "2") (pinfunction "2_2") (pintype "passive"))
    )
    (net (code "84") (name "Net-(Q25-C)") (class "Default")
      (node (ref "Q25") (pin "3") (pinfunction "C_3") (pintype "passive"))
      (node (ref "R64") (pin "1") (pinfunction "1_1") (pintype "passive"))
    )
    (net (code "85") (name "Net-(Q25-E)") (class "Default")
      (node (ref "C14") (pin "2") (pinfunction "2_2") (pintype "passive"))
      (node (ref "Q25") (pin "1") (pinfunction "E_1") (pintype "passive"))
      (node (ref "R61") (pin "2") (pinfunction "2_2") (pintype "passive"))
      (node (ref "R63") (pin "2") (pinfunction "2_2") (pintype "passive"))
    )
    (net (code "86") (name "Net-(Q26A-B)") (class "Default")
      (node (ref "D33") (pin "A") (pinfunction "A_A") (pintype "passive"))
      (node (ref "Q26") (pin "2") (pinfunction "B_2") (pintype "passive"))
      (node (ref "R67") (pin "2") (pinfunction "2_2") (pintype "passive"))
    )
    (net (code "87") (name "Net-(Q26A-E)") (class "Default")
      (node (ref "Q26") (pin "3") (pinfunction "E_3") (pintype "passive"))
      (node (ref "Q26") (pin "4") (pinfunction "E_4") (pintype "passive"))
      (node (ref "R66") (pin "1") (pinfunction "1_1") (pintype "passive"))
    )
    (net (code "88") (name "Net-(Q26B-B)") (class "Default")
      (node (ref "Q26") (pin "5") (pinfunction "B_5") (pintype "passive"))
      (node (ref "R56") (pin "2") (pinfunction "2_2") (pintype "passive"))
      (node (ref "R57") (pin "1") (pinfunction "1_1") (pintype "passive"))
    )
    (net (code "89") (name "VCC") (class "Default")
      (node (ref "C15") (pin "+") (pinfunction "+_+") (pintype "passive"))
      (node (ref "Q21") (pin "6") (pinfunction "C_6") (pintype "passive"))
      (node (ref "R53") (pin "2") (pinfunction "2_2") (pintype "passive"))
      (node (ref "R64") (pin "2") (pinfunction "2_2") (pintype "passive"))
      (node (ref "U$2") (pin "AA2") (pinfunction "1_AA2") (pintype "bidirectional"))
    )
    (net (code "90") (name "unconnected-(E1A-PRE-Pad4)") (class "Default")
      (node (ref "E1") (pin "4") (pinfunction "PRE_4") (pintype "input"))
    )
    (net (code "91") (name "unconnected-(E1A-Q-Pad5)") (class "Default")
      (node (ref "E1") (pin "5") (pinfunction "Q_5") (pintype "output"))
    )
    (net (code "92") (name "unconnected-(E1B-PRE-Pad10)") (class "Default")
      (node (ref "E1") (pin "10") (pinfunction "PRE_10") (pintype "input"))
    )
    (net (code "93") (name "unconnected-(E1B-Q-Pad9)") (class "Default")
      (node (ref "E1") (pin "9") (pinfunction "Q_9") (pintype "output"))
    )
    (net (code "94") (name "unconnected-(E2A-PRE-Pad4)") (class "Default")
      (node (ref "E2") (pin "4") (pinfunction "PRE_4") (pintype "input"))
    )
    (net (code "95") (name "unconnected-(E2A-Q-Pad5)") (class "Default")
      (node (ref "E2") (pin "5") (pinfunction "Q_5") (pintype "output"))
    )
    (net (code "96") (name "unconnected-(E2B-PRE-Pad10)") (class "Default")
      (node (ref "E2") (pin "10") (pinfunction "PRE_10") (pintype "input"))
    )
    (net (code "97") (name "unconnected-(E2B-Q-Pad9)") (class "Default")
      (node (ref "E2") (pin "9") (pinfunction "Q_9") (pintype "output"))
    )
    (net (code "98") (name "unconnected-(E3A-PRE-Pad4)") (class "Default")
      (node (ref "E3") (pin "4") (pinfunction "PRE_4") (pintype "input"))
    )
    (net (code "99") (name "unconnected-(E3A-Q-Pad5)") (class "Default")
      (node (ref "E3") (pin "5") (pinfunction "Q_5") (pintype "output"))
    )
    (net (code "100") (name "unconnected-(E3B-PRE-Pad10)") (class "Default")
      (node (ref "E3") (pin "10") (pinfunction "PRE_10") (pintype "input"))
    )
    (net (code "101") (name "unconnected-(E3B-Q-Pad9)") (class "Default")
      (node (ref "E3") (pin "9") (pinfunction "Q_9") (pintype "output"))
    )
    (net (code "102") (name "unconnected-(E4A-PRE-Pad4)") (class "Default")
      (node (ref "E4") (pin "4") (pinfunction "PRE_4") (pintype "input"))
    )
    (net (code "103") (name "unconnected-(E4A-Q-Pad5)") (class "Default")
      (node (ref "E4") (pin "5") (pinfunction "Q_5") (pintype "output"))
    )
    (net (code "104") (name "unconnected-(E4B-PRE-Pad10)") (class "Default")
      (node (ref "E4") (pin "10") (pinfunction "PRE_10") (pintype "input"))
    )
    (net (code "105") (name "unconnected-(E4B-Q-Pad9)") (class "Default")
      (node (ref "E4") (pin "9") (pinfunction "Q_9") (pintype "output"))
    )
    (net (code "106") (name "unconnected-(E5A-PRE-Pad4)") (class "Default")
      (node (ref "E5") (pin "4") (pinfunction "PRE_4") (pintype "input"))
    )
    (net (code "107") (name "unconnected-(E5A-Q-Pad5)") (class "Default")
      (node (ref "E5") (pin "5") (pinfunction "Q_5") (pintype "output"))
    )
    (net (code "108") (name "unconnected-(E5B-PRE-Pad10)") (class "Default")
      (node (ref "E5") (pin "10") (pinfunction "PRE_10") (pintype "input"))
    )
    (net (code "109") (name "unconnected-(E5B-Q-Pad9)") (class "Default")
      (node (ref "E5") (pin "9") (pinfunction "Q_9") (pintype "output"))
    )
  )
)
